# schematic.net
KiCad netlist of a schematic drawn in EasyEDA
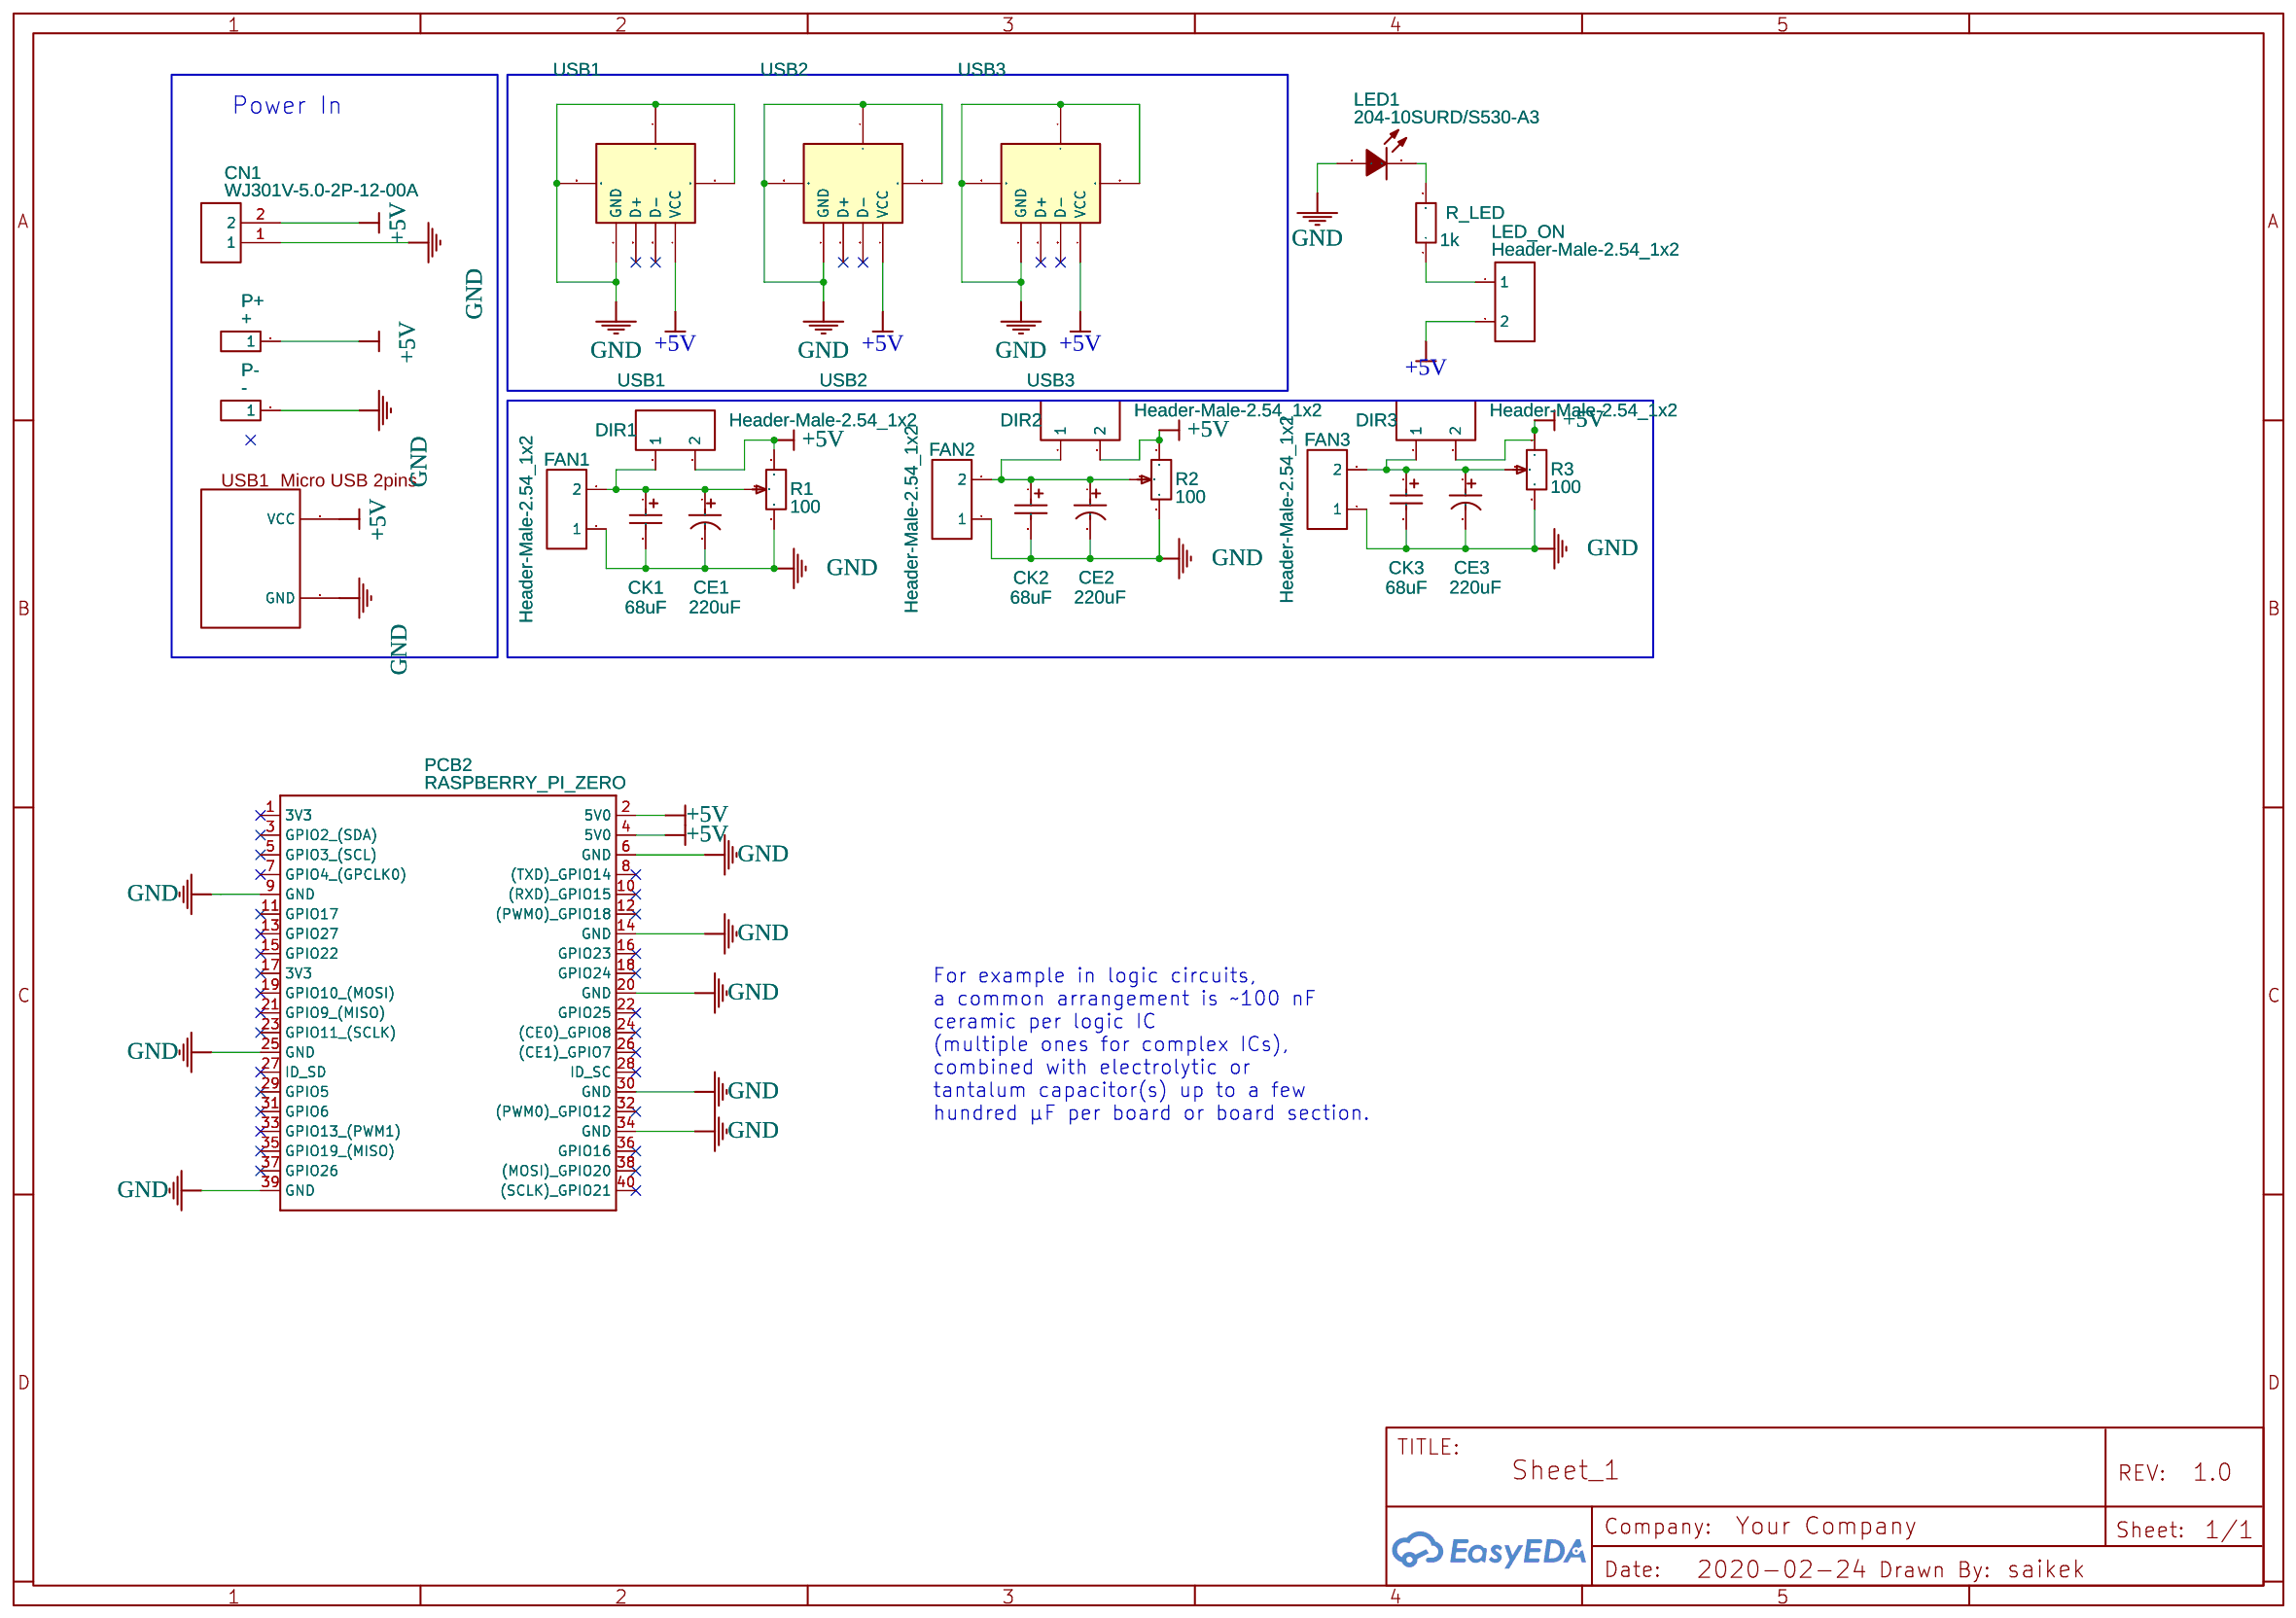
[diagram p0: schematic sheet]

(export (version "E")
  (design (tool "Eeschema 10.0.6"))
  (components
    (comp (ref "CE1")
      (value "220uF")
      (fields
        (field (name "BOM_Manufacturer Part") "220uF 16V 6.3*11")
        (field (name "BOM_Supplier Part") "C43349")
      )
      (libsource (lib "") (part "220uF 16V 6.3*11"))
    )
    (comp (ref "CE2")
      (value "220uF")
      (fields
        (field (name "BOM_Manufacturer Part") "220uF 16V 6.3*11")
        (field (name "BOM_Supplier Part") "C43349")
      )
      (libsource (lib "") (part "220uF 16V 6.3*11"))
    )
    (comp (ref "CE3")
      (value "220uF")
      (fields
        (field (name "BOM_Manufacturer Part") "220uF 16V 6.3*11")
        (field (name "BOM_Supplier Part") "C43349")
      )
      (libsource (lib "") (part "220uF 16V 6.3*11"))
    )
    (comp (ref "CK1")
      (value "68uF")
      (fields
        (field (name "BOM_Manufacturer Part") "TAJC686K016RNJ")
        (field (name "BOM_Supplier Part") "C7220")
      )
      (libsource (lib "") (part "TAJC686K016RNJ"))
    )
    (comp (ref "CK2")
      (value "68uF")
      (fields
        (field (name "BOM_Manufacturer Part") "TAJC686K016RNJ")
        (field (name "BOM_Supplier Part") "C7220")
      )
      (libsource (lib "") (part "TAJC686K016RNJ"))
    )
    (comp (ref "CK3")
      (value "68uF")
      (fields
        (field (name "BOM_Manufacturer Part") "TAJC686K016RNJ")
        (field (name "BOM_Supplier Part") "C7220")
      )
      (libsource (lib "") (part "TAJC686K016RNJ"))
    )
    (comp (ref "CN1")
      (value "WJ301V-5.0-2P-12-00A")
      (fields
        (field (name "BOM_Manufacturer Part") "WJ301V-5.0-2P")
        (field (name "BOM_Supplier Part") "C8475")
      )
      (libsource (lib "") (part "Unknown_115_-695"))
    )
    (comp (ref "DIR1")
      (value "Header-Male-2.54_1x2")
      (fields (field (name "BOM_Manufacturer Part") "826629-2") (field (name "BOM_Supplier Part") "C225488"))
      (libsource (lib "") (part "Unknown_335_-590"))
    )
    (comp (ref "DIR2")
      (value "Header-Male-2.54_1x2")
      (fields (field (name "BOM_Manufacturer Part") "826629-2") (field (name "BOM_Supplier Part") "C225488"))
      (libsource (lib "") (part "Unknown_540_-595"))
    )
    (comp (ref "DIR3")
      (value "Header-Male-2.54_1x2")
      (fields (field (name "BOM_Manufacturer Part") "826629-2") (field (name "BOM_Supplier Part") "C225488"))
      (libsource (lib "") (part "Unknown_720_-595"))
    )
    (comp (ref "FAN1")
      (value "Header-Male-2.54_1x2")
      (fields (field (name "BOM_Manufacturer Part") "826629-2") (field (name "BOM_Supplier Part") "C225488"))
      (libsource (lib "") (part "Unknown_285_-555"))
    )
    (comp (ref "FAN2")
      (value "Header-Male-2.54_1x2")
      (fields (field (name "BOM_Manufacturer Part") "826629-2") (field (name "BOM_Supplier Part") "C225488"))
      (libsource (lib "") (part "Unknown_480_-560"))
    )
    (comp (ref "FAN3")
      (value "Header-Male-2.54_1x2")
      (fields (field (name "BOM_Manufacturer Part") "826629-2") (field (name "BOM_Supplier Part") "C225488"))
      (libsource (lib "") (part "Unknown_670_-565"))
    )
    (comp (ref "LED1")
      (value "204-10SURD/S530-A3")
      (fields (field (name "BOM_Supplier Part") "C99772"))
      (libsource (lib "") (part "204-10SURD/S530-A3"))
    )
    (comp (ref "LED_ON")
      (value "Header-Male-2.54_1x2")
      (fields (field (name "BOM_Manufacturer Part") "826629-2") (field (name "BOM_Supplier Part") "C86471"))
      (libsource (lib "") (part "Header-Male-2.54_1x2"))
    )
    (comp (ref "P+")
      (value "+")
      (fields
        (field (name "BOM_Manufacturer Part") "Header-Male-2.54_1x1")
        (field (name "BOM_Supplier Part") "C81276")
      )
      (libsource (lib "") (part "Unknown_120_-640"))
    )
    (comp (ref "P-")
      (value "-")
      (fields
        (field (name "BOM_Manufacturer Part") "Header-Male-2.54_1x1")
        (field (name "BOM_Supplier Part") "C81276")
      )
      (libsource (lib "") (part "Unknown_120_-605"))
    )
    (comp (ref "PCB2")
      (value "RASPBERRY_PI_ZERO")
      (fields (field (name "BOM_Manufacturer Part") "?"))
      (libsource (lib "") (part "Unknown_225_-310"))
    )
    (comp (ref "R1")
      (value "100")
      (fields
        (field (name "BOM_Manufacturer Part") "3296X-1-101LF")
        (field (name "BOM_Supplier Part") "C92220")
      )
      (libsource (lib "") (part "3296X-1-101LF"))
    )
    (comp (ref "R2")
      (value "100")
      (fields
        (field (name "BOM_Manufacturer Part") "3296X-1-101LF")
        (field (name "BOM_Supplier Part") "C92220")
      )
      (libsource (lib "") (part "3296X-1-101LF"))
    )
    (comp (ref "R3")
      (value "100")
      (fields
        (field (name "BOM_Manufacturer Part") "3296X-1-101LF")
        (field (name "BOM_Supplier Part") "C92220")
      )
      (libsource (lib "") (part "3296X-1-101LF"))
    )
    (comp (ref "R_LED") (value "1k") (libsource (lib "") (part "Res_1206(1/4W)_EU")))
    (comp (ref "U2") (value "MicroUSB 2 pins female") (libsource (lib "") (part "Unknown_125_-530")))
    (comp (ref "USB1")
      (value "USB1")
      (fields
        (field (name "BOM_Manufacturer Part") "AF 10.0 Side insert 3 Boundless iron PBT White plastic 90degree")
        (field (name "BOM_Supplier Part") "C39451")
      )
      (libsource (lib "") (part "AF 10.0 Side insert 3 Boundless iron PBT White plastic 90degree"))
    )
    (comp (ref "USB2")
      (value "USB2")
      (fields
        (field (name "BOM_Manufacturer Part") "AF 10.0 Side insert 3 Boundless iron PBT White plastic 90degree")
        (field (name "BOM_Supplier Part") "C39451")
      )
      (libsource (lib "") (part "AF 10.0 Side insert 3 Boundless iron PBT White plastic 90degree"))
    )
    (comp (ref "USB3")
      (value "USB3")
      (fields
        (field (name "BOM_Manufacturer Part") "AF 10.0 Side insert 3 Boundless iron PBT White plastic 90degree")
        (field (name "BOM_Supplier Part") "C39451")
      )
      (libsource (lib "") (part "AF 10.0 Side insert 3 Boundless iron PBT White plastic 90degree"))
    )
  )
  (nets
    (net (code "1") (name "+5V") (class "Default")
      (node (ref "CN1") (pin "2") (pinfunction "2_2") (pintype "unspecified"))
      (node (ref "DIR1") (pin "2") (pinfunction "2_2") (pintype "unspecified"))
      (node (ref "DIR2") (pin "2") (pinfunction "2_2") (pintype "unspecified"))
      (node (ref "DIR3") (pin "2") (pinfunction "2_2") (pintype "unspecified"))
      (node (ref "LED_ON") (pin "2") (pinfunction "2_2") (pintype "unspecified"))
      (node (ref "P+") (pin "1") (pinfunction "1_1") (pintype "input"))
      (node (ref "PCB2") (pin "2") (pinfunction "5V0_2") (pintype "unspecified"))
      (node (ref "PCB2") (pin "4") (pinfunction "5V0_4") (pintype "unspecified"))
      (node (ref "R1") (pin "1") (pinfunction "1_1") (pintype "input"))
      (node (ref "R2") (pin "1") (pinfunction "1_1") (pintype "input"))
      (node (ref "R3") (pin "1") (pinfunction "1_1") (pintype "input"))
      (node (ref "U2") (pin "2") (pinfunction "VCC_2") (pintype "unspecified"))
      (node (ref "USB1") (pin "4") (pinfunction "VCC_4") (pintype "input"))
      (node (ref "USB2") (pin "4") (pinfunction "VCC_4") (pintype "input"))
      (node (ref "USB3") (pin "4") (pinfunction "VCC_4") (pintype "input"))
    )
    (net (code "2") (name "GND") (class "Default")
      (node (ref "CE1") (pin "2") (pinfunction "2_2") (pintype "input"))
      (node (ref "CE2") (pin "2") (pinfunction "2_2") (pintype "input"))
      (node (ref "CE3") (pin "2") (pinfunction "2_2") (pintype "input"))
      (node (ref "CK1") (pin "2") (pinfunction "2_2") (pintype "input"))
      (node (ref "CK2") (pin "2") (pinfunction "2_2") (pintype "input"))
      (node (ref "CK3") (pin "2") (pinfunction "2_2") (pintype "input"))
      (node (ref "CN1") (pin "1") (pinfunction "1_1") (pintype "unspecified"))
      (node (ref "FAN1") (pin "1") (pinfunction "1_1") (pintype "unspecified"))
      (node (ref "FAN2") (pin "1") (pinfunction "1_1") (pintype "unspecified"))
      (node (ref "FAN3") (pin "1") (pinfunction "1_1") (pintype "unspecified"))
      (node (ref "LED1") (pin "1") (pinfunction "A_1") (pintype "unspecified"))
      (node (ref "P-") (pin "1") (pinfunction "1_1") (pintype "input"))
      (node (ref "PCB2") (pin "14") (pinfunction "GND_14") (pintype "unspecified"))
      (node (ref "PCB2") (pin "20") (pinfunction "GND_20") (pintype "unspecified"))
      (node (ref "PCB2") (pin "25") (pinfunction "GND_25") (pintype "unspecified"))
      (node (ref "PCB2") (pin "30") (pinfunction "GND_30") (pintype "unspecified"))
      (node (ref "PCB2") (pin "34") (pinfunction "GND_34") (pintype "unspecified"))
      (node (ref "PCB2") (pin "39") (pinfunction "GND_39") (pintype "unspecified"))
      (node (ref "PCB2") (pin "6") (pinfunction "GND_6") (pintype "unspecified"))
      (node (ref "PCB2") (pin "9") (pinfunction "GND_9") (pintype "unspecified"))
      (node (ref "R1") (pin "3") (pinfunction "3_3") (pintype "input"))
      (node (ref "R2") (pin "3") (pinfunction "3_3") (pintype "input"))
      (node (ref "R3") (pin "3") (pinfunction "3_3") (pintype "input"))
      (node (ref "U2") (pin "1") (pinfunction "GND_1") (pintype "unspecified"))
      (node (ref "USB1") (pin "1") (pinfunction "GND_1") (pintype "input"))
      (node (ref "USB1") (pin "5") (pinfunction "5_5") (pintype "unspecified"))
      (node (ref "USB1") (pin "6") (pinfunction "6_6") (pintype "unspecified"))
      (node (ref "USB1") (pin "7") (pinfunction "7_7") (pintype "unspecified"))
      (node (ref "USB2") (pin "1") (pinfunction "GND_1") (pintype "input"))
      (node (ref "USB2") (pin "5") (pinfunction "5_5") (pintype "unspecified"))
      (node (ref "USB2") (pin "6") (pinfunction "6_6") (pintype "unspecified"))
      (node (ref "USB2") (pin "7") (pinfunction "7_7") (pintype "unspecified"))
      (node (ref "USB3") (pin "1") (pinfunction "GND_1") (pintype "input"))
      (node (ref "USB3") (pin "5") (pinfunction "5_5") (pintype "unspecified"))
      (node (ref "USB3") (pin "6") (pinfunction "6_6") (pintype "unspecified"))
      (node (ref "USB3") (pin "7") (pinfunction "7_7") (pintype "unspecified"))
    )
    (net (code "3") (name "Net-(CE1-Pad1)") (class "Default")
      (node (ref "CE1") (pin "1") (pinfunction "1_1") (pintype "input"))
      (node (ref "CK1") (pin "1") (pinfunction "1_1") (pintype "input"))
      (node (ref "DIR1") (pin "1") (pinfunction "1_1") (pintype "unspecified"))
      (node (ref "FAN1") (pin "2") (pinfunction "2_2") (pintype "unspecified"))
      (node (ref "R1") (pin "2") (pinfunction "2_2") (pintype "input"))
    )
    (net (code "4") (name "Net-(CE2-Pad1)") (class "Default")
      (node (ref "CE2") (pin "1") (pinfunction "1_1") (pintype "input"))
      (node (ref "CK2") (pin "1") (pinfunction "1_1") (pintype "input"))
      (node (ref "DIR2") (pin "1") (pinfunction "1_1") (pintype "unspecified"))
      (node (ref "FAN2") (pin "2") (pinfunction "2_2") (pintype "unspecified"))
      (node (ref "R2") (pin "2") (pinfunction "2_2") (pintype "input"))
    )
    (net (code "5") (name "Net-(CE3-Pad1)") (class "Default")
      (node (ref "CE3") (pin "1") (pinfunction "1_1") (pintype "input"))
      (node (ref "CK3") (pin "1") (pinfunction "1_1") (pintype "input"))
      (node (ref "DIR3") (pin "1") (pinfunction "1_1") (pintype "unspecified"))
      (node (ref "FAN3") (pin "2") (pinfunction "2_2") (pintype "unspecified"))
      (node (ref "R3") (pin "2") (pinfunction "2_2") (pintype "input"))
    )
    (net (code "6") (name "Net-(LED1-K)") (class "Default")
      (node (ref "LED1") (pin "2") (pinfunction "K_2") (pintype "unspecified"))
      (node (ref "R_LED") (pin "2") (pinfunction "2_2") (pintype "unspecified"))
    )
    (net (code "7") (name "Net-(LED_ON-Pad1)") (class "Default")
      (node (ref "LED_ON") (pin "1") (pinfunction "1_1") (pintype "unspecified"))
      (node (ref "R_LED") (pin "1") (pinfunction "1_1") (pintype "unspecified"))
    )
    (net (code "8") (name "unconnected-(PCB2-(CE0)_GPIO8-Pad24)") (class "Default")
      (node (ref "PCB2") (pin "24") (pinfunction "(CE0)_GPIO8_24") (pintype "unspecified+no_connect"))
    )
    (net (code "9") (name "unconnected-(PCB2-(CE1)_GPIO7-Pad26)") (class "Default")
      (node (ref "PCB2") (pin "26") (pinfunction "(CE1)_GPIO7_26") (pintype "unspecified+no_connect"))
    )
    (net (code "10") (name "unconnected-(PCB2-(MOSI)_GPIO20-Pad38)") (class "Default")
      (node (ref "PCB2") (pin "38") (pinfunction "(MOSI)_GPIO20_38") (pintype "unspecified+no_connect"))
    )
    (net (code "11") (name "unconnected-(PCB2-(PWM0)_GPIO12-Pad32)") (class "Default")
      (node (ref "PCB2") (pin "32") (pinfunction "(PWM0)_GPIO12_32") (pintype "unspecified+no_connect"))
    )
    (net (code "12") (name "unconnected-(PCB2-(PWM0)_GPIO18-Pad12)") (class "Default")
      (node (ref "PCB2") (pin "12") (pinfunction "(PWM0)_GPIO18_12") (pintype "unspecified+no_connect"))
    )
    (net (code "13") (name "unconnected-(PCB2-(RXD)_GPIO15-Pad10)") (class "Default")
      (node (ref "PCB2") (pin "10") (pinfunction "(RXD)_GPIO15_10") (pintype "unspecified+no_connect"))
    )
    (net (code "14") (name "unconnected-(PCB2-(SCLK)_GPIO21-Pad40)") (class "Default")
      (node (ref "PCB2") (pin "40") (pinfunction "(SCLK)_GPIO21_40") (pintype "unspecified+no_connect"))
    )
    (net (code "15") (name "unconnected-(PCB2-(TXD)_GPIO14-Pad8)") (class "Default")
      (node (ref "PCB2") (pin "8") (pinfunction "(TXD)_GPIO14_8") (pintype "unspecified+no_connect"))
    )
    (net (code "16") (name "unconnected-(PCB2-3V3-Pad1)") (class "Default")
      (node (ref "PCB2") (pin "1") (pinfunction "3V3_1") (pintype "unspecified+no_connect"))
    )
    (net (code "17") (name "unconnected-(PCB2-3V3-Pad17)") (class "Default")
      (node (ref "PCB2") (pin "17") (pinfunction "3V3_17") (pintype "unspecified+no_connect"))
    )
    (net (code "18") (name "unconnected-(PCB2-GPIO2_(SDA)-Pad3)") (class "Default")
      (node (ref "PCB2") (pin "3") (pinfunction "GPIO2_(SDA)_3") (pintype "unspecified+no_connect"))
    )
    (net (code "19") (name "unconnected-(PCB2-GPIO3_(SCL)-Pad5)") (class "Default")
      (node (ref "PCB2") (pin "5") (pinfunction "GPIO3_(SCL)_5") (pintype "unspecified+no_connect"))
    )
    (net (code "20") (name "unconnected-(PCB2-GPIO4_(GPCLK0)-Pad7)") (class "Default")
      (node (ref "PCB2") (pin "7") (pinfunction "GPIO4_(GPCLK0)_7") (pintype "unspecified+no_connect"))
    )
    (net (code "21") (name "unconnected-(PCB2-GPIO5-Pad29)") (class "Default")
      (node (ref "PCB2") (pin "29") (pinfunction "GPIO5_29") (pintype "unspecified+no_connect"))
    )
    (net (code "22") (name "unconnected-(PCB2-GPIO6-Pad31)") (class "Default")
      (node (ref "PCB2") (pin "31") (pinfunction "GPIO6_31") (pintype "unspecified+no_connect"))
    )
    (net (code "23") (name "unconnected-(PCB2-GPIO9_(MISO)-Pad21)") (class "Default")
      (node (ref "PCB2") (pin "21") (pinfunction "GPIO9_(MISO)_21") (pintype "unspecified+no_connect"))
    )
    (net (code "24") (name "unconnected-(PCB2-GPIO10_(MOSI)-Pad19)") (class "Default")
      (node (ref "PCB2") (pin "19") (pinfunction "GPIO10_(MOSI)_19") (pintype "unspecified+no_connect"))
    )
    (net (code "25") (name "unconnected-(PCB2-GPIO11_(SCLK)-Pad23)") (class "Default")
      (node (ref "PCB2") (pin "23") (pinfunction "GPIO11_(SCLK)_23") (pintype "unspecified+no_connect"))
    )
    (net (code "26") (name "unconnected-(PCB2-GPIO13_(PWM1)-Pad33)") (class "Default")
      (node (ref "PCB2") (pin "33") (pinfunction "GPIO13_(PWM1)_33") (pintype "unspecified+no_connect"))
    )
    (net (code "27") (name "unconnected-(PCB2-GPIO16-Pad36)") (class "Default")
      (node (ref "PCB2") (pin "36") (pinfunction "GPIO16_36") (pintype "unspecified+no_connect"))
    )
    (net (code "28") (name "unconnected-(PCB2-GPIO17-Pad11)") (class "Default")
      (node (ref "PCB2") (pin "11") (pinfunction "GPIO17_11") (pintype "unspecified+no_connect"))
    )
    (net (code "29") (name "unconnected-(PCB2-GPIO19_(MISO)-Pad35)") (class "Default")
      (node (ref "PCB2") (pin "35") (pinfunction "GPIO19_(MISO)_35") (pintype "unspecified+no_connect"))
    )
    (net (code "30") (name "unconnected-(PCB2-GPIO22-Pad15)") (class "Default")
      (node (ref "PCB2") (pin "15") (pinfunction "GPIO22_15") (pintype "unspecified+no_connect"))
    )
    (net (code "31") (name "unconnected-(PCB2-GPIO23-Pad16)") (class "Default")
      (node (ref "PCB2") (pin "16") (pinfunction "GPIO23_16") (pintype "unspecified+no_connect"))
    )
    (net (code "32") (name "unconnected-(PCB2-GPIO24-Pad18)") (class "Default")
      (node (ref "PCB2") (pin "18") (pinfunction "GPIO24_18") (pintype "unspecified+no_connect"))
    )
    (net (code "33") (name "unconnected-(PCB2-GPIO25-Pad22)") (class "Default")
      (node (ref "PCB2") (pin "22") (pinfunction "GPIO25_22") (pintype "unspecified+no_connect"))
    )
    (net (code "34") (name "unconnected-(PCB2-GPIO26-Pad37)") (class "Default")
      (node (ref "PCB2") (pin "37") (pinfunction "GPIO26_37") (pintype "unspecified+no_connect"))
    )
    (net (code "35") (name "unconnected-(PCB2-GPIO27-Pad13)") (class "Default")
      (node (ref "PCB2") (pin "13") (pinfunction "GPIO27_13") (pintype "unspecified+no_connect"))
    )
    (net (code "36") (name "unconnected-(PCB2-ID_SC-Pad28)") (class "Default")
      (node (ref "PCB2") (pin "28") (pinfunction "ID_SC_28") (pintype "unspecified+no_connect"))
    )
    (net (code "37") (name "unconnected-(PCB2-ID_SD-Pad27)") (class "Default")
      (node (ref "PCB2") (pin "27") (pinfunction "ID_SD_27") (pintype "unspecified+no_connect"))
    )
    (net (code "38") (name "unconnected-(USB1-D+-Pad2)") (class "Default")
      (node (ref "USB1") (pin "2") (pinfunction "D+_2") (pintype "input+no_connect"))
    )
    (net (code "39") (name "unconnected-(USB1-D--Pad3)") (class "Default")
      (node (ref "USB1") (pin "3") (pinfunction "D-_3") (pintype "input+no_connect"))
    )
    (net (code "40") (name "unconnected-(USB2-D+-Pad2)") (class "Default")
      (node (ref "USB2") (pin "2") (pinfunction "D+_2") (pintype "input+no_connect"))
    )
    (net (code "41") (name "unconnected-(USB2-D--Pad3)") (class "Default")
      (node (ref "USB2") (pin "3") (pinfunction "D-_3") (pintype "input+no_connect"))
    )
    (net (code "42") (name "unconnected-(USB3-D+-Pad2)") (class "Default")
      (node (ref "USB3") (pin "2") (pinfunction "D+_2") (pintype "input+no_connect"))
    )
    (net (code "43") (name "unconnected-(USB3-D--Pad3)") (class "Default")
      (node (ref "USB3") (pin "3") (pinfunction "D-_3") (pintype "input+no_connect"))
    )
  )
)
